# relay.net
KiCad netlist of a schematic drawn in Altium Designer
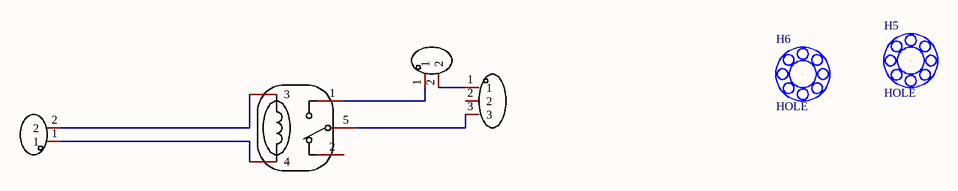
[diagram p0: relay.SchDoc]

(export (version "E")
  (design (tool "Eeschema 10.0.6"))
  (components
    (comp (ref "H5")
      (value "HOLE")
      (footprint "zq:HOLE_3.5mm_MUL")
      (description "固定孔")
      (libsource (lib "zq") (part "HOLE"))
    )
    (comp (ref "H6")
      (value "HOLE")
      (footprint "zq:HOLE_3.5mm_MUL")
      (description "固定孔")
      (libsource (lib "zq") (part "HOLE"))
    )
    (comp (ref "K1")
      (value "SRA-12VDC-CL")
      (footprint "zq:RELAY-TH_SRA-X-CX")
      (description "12v")
      (fields (field (name "MANUFACTURER") "松乐"))
      (libsource (lib "zq") (part "继电器"))
    )
    (comp (ref "p16")
      (value "ZX-VH3.96-2PZZ")
      (footprint "zq:CONN-TH_2P-P3.96_MEGASTAR_ZX-VH3.96-2PZZ")
      (description "2p")
      (fields (field (name "MANUFACTURER") "Megastar(兆星)"))
      (libsource (lib "zq") (part "VH3.96-2PZZ"))
    )
    (comp (ref "p17")
      (value "ZX-VH3.96-3PZZ")
      (footprint "zq:CONN-TH_3P-P3.96_FWF39601-S03S22W1B")
      (fields (field (name "MANUFACTURER") "SHOU HAN(首韩)") (field (name "MANUFACTURER PART") "VH3.96-3P ZZ"))
      (libsource (lib "zq") (part "VH3.96-3P ZZ"))
    )
    (comp (ref "P18")
      (value "ZX-HY2.0-2PZZ")
      (footprint "zq:CONN-TH_2P-P2.00_ZX-HY2.0-2PZZ")
      (description "2p")
      (fields (field (name "MANUFACTURER") "Megastar(兆星)"))
      (libsource (lib "zq") (part "HY2.0-2PZZ"))
    )
  )
  (nets
    (net (code "1") (name "Net-(K1-Pad1)") (class "Default")
      (node (ref "K1") (pin "1") (pinfunction "1_1") (pintype "passive"))
      (node (ref "p16") (pin "1") (pinfunction "1_1") (pintype "passive"))
    )
    (net (code "2") (name "Net-(K1-Pad3)") (class "Default")
      (node (ref "K1") (pin "3") (pinfunction "3_3") (pintype "passive"))
      (node (ref "P18") (pin "2") (pinfunction "2_2") (pintype "passive"))
    )
    (net (code "3") (name "Net-(K1-Pad4)") (class "Default")
      (node (ref "K1") (pin "4") (pinfunction "4_4") (pintype "passive"))
      (node (ref "P18") (pin "1") (pinfunction "1_1") (pintype "passive"))
    )
    (net (code "4") (name "Net-(K1-Pad5)") (class "Default")
      (node (ref "K1") (pin "5") (pinfunction "5_5") (pintype "passive"))
      (node (ref "p17") (pin "3") (pinfunction "3_3") (pintype "passive"))
    )
    (net (code "5") (name "Net-(p16-Pad2)") (class "Default")
      (node (ref "p16") (pin "2") (pinfunction "2_2") (pintype "passive"))
      (node (ref "p17") (pin "1") (pinfunction "1_1") (pintype "passive"))
    )
    (net (code "6") (name "unconnected-(H5-Pad1)") (class "Default")
      (node (ref "H5") (pin "1") (pinfunction "1_1") (pintype "passive"))
    )
    (net (code "7") (name "unconnected-(H6-Pad1)") (class "Default")
      (node (ref "H6") (pin "1") (pinfunction "1_1") (pintype "passive"))
    )
    (net (code "8") (name "unconnected-(K1-Pad2)") (class "Default")
      (node (ref "K1") (pin "2") (pinfunction "2_2") (pintype "passive"))
    )
    (net (code "9") (name "unconnected-(p17-Pad2)") (class "Default")
      (node (ref "p17") (pin "2") (pinfunction "2_2") (pintype "passive"))
    )
  )
)
